# Teensy36_CAN_Bus.net
KiCad netlist of a schematic drawn in EAGLE
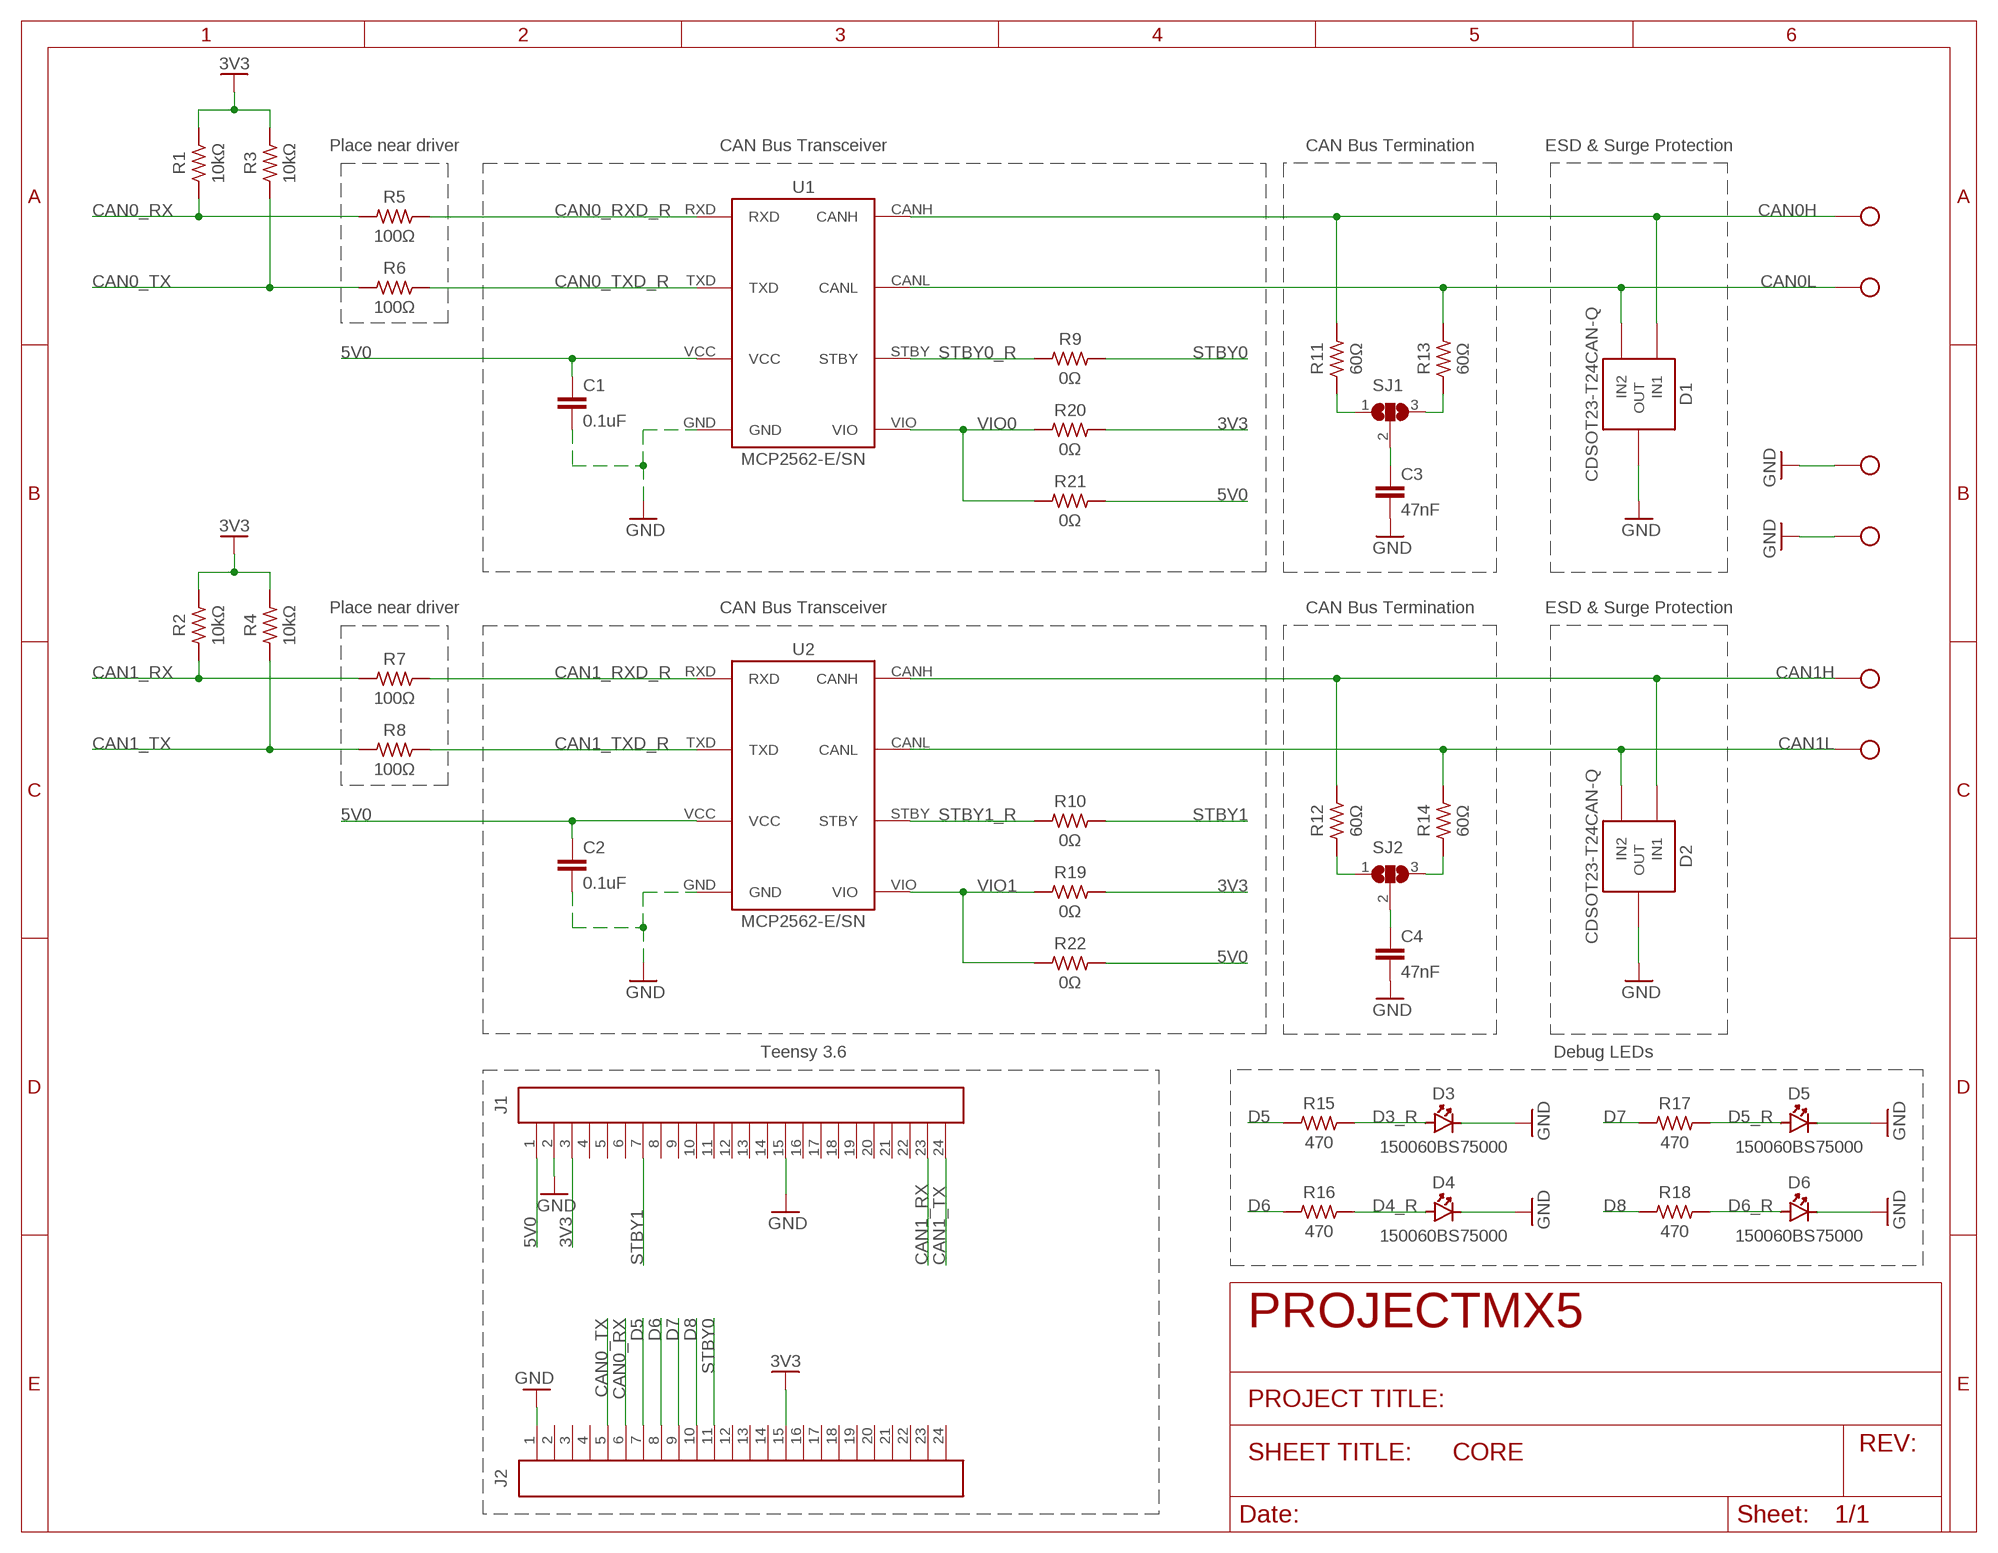
[diagram p0: schematic, sheet 1]

(export (version "E")
  (design (tool "Eeschema 10.0.6"))
  (components
    (comp (ref "C1")
      (value "0.1uF")
      (footprint "eagle-import:CAP-0603")
      (libsource (lib "eagle-import") (part "CAPACITOR0603"))
    )
    (comp (ref "C2")
      (value "0.1uF")
      (footprint "eagle-import:CAP-0603")
      (libsource (lib "eagle-import") (part "CAPACITOR0603"))
    )
    (comp (ref "C3")
      (value "47nF")
      (footprint "eagle-import:CAP-0603")
      (libsource (lib "eagle-import") (part "CAPACITOR0603"))
    )
    (comp (ref "C4")
      (value "47nF")
      (footprint "eagle-import:CAP-0603")
      (libsource (lib "eagle-import") (part "CAPACITOR0603"))
    )
    (comp (ref "D1")
      (value "CDSOT23-T24CAN-Q")
      (footprint "eagle-import:BOURNS_CDSOT23-T24CAN-Q")
      (libsource (lib "eagle-import") (part "BOURNS_CDSOT23-T24CAN-Q"))
    )
    (comp (ref "D2")
      (value "CDSOT23-T24CAN-Q")
      (footprint "eagle-import:BOURNS_CDSOT23-T24CAN-Q")
      (libsource (lib "eagle-import") (part "BOURNS_CDSOT23-T24CAN-Q"))
    )
    (comp (ref "D3")
      (value "LED_BLUE_0603_WURTH")
      (footprint "eagle-import:WURTH_0603_LED")
      (fields (field (name "PN") "150060BS75000") (field (name "MFG") "WURTH ELEKTRONIK"))
      (libsource (lib "eagle-import") (part "LED_BLUE_0603_WURTH"))
    )
    (comp (ref "D4")
      (value "LED_BLUE_0603_WURTH")
      (footprint "eagle-import:WURTH_0603_LED")
      (fields (field (name "PN") "150060BS75000") (field (name "MFG") "WURTH ELEKTRONIK"))
      (libsource (lib "eagle-import") (part "LED_BLUE_0603_WURTH"))
    )
    (comp (ref "D5")
      (value "LED_BLUE_0603_WURTH")
      (footprint "eagle-import:WURTH_0603_LED")
      (fields (field (name "PN") "150060BS75000") (field (name "MFG") "WURTH ELEKTRONIK"))
      (libsource (lib "eagle-import") (part "LED_BLUE_0603_WURTH"))
    )
    (comp (ref "D6")
      (value "LED_BLUE_0603_WURTH")
      (footprint "eagle-import:WURTH_0603_LED")
      (fields (field (name "PN") "150060BS75000") (field (name "MFG") "WURTH ELEKTRONIK"))
      (libsource (lib "eagle-import") (part "LED_BLUE_0603_WURTH"))
    )
    (comp (ref "J1")
      (value "CONN_24PIN_VERT")
      (footprint "eagle-import:CONN_100MIL_24_PIN")
      (libsource (lib "eagle-import") (part "CONN_24PIN_VERT"))
    )
    (comp (ref "J2")
      (value "CONN_24PIN_VERT")
      (footprint "eagle-import:CONN_100MIL_24_PIN")
      (libsource (lib "eagle-import") (part "CONN_24PIN_VERT"))
    )
    (comp (ref "J3")
      (value "SOLDER_POINT")
      (footprint "eagle-import:SMD_PAD_100X200")
      (libsource (lib "eagle-import") (part "SOLDER_POINT"))
    )
    (comp (ref "J4")
      (value "SOLDER_POINT")
      (footprint "eagle-import:SMD_PAD_100X200")
      (libsource (lib "eagle-import") (part "SOLDER_POINT"))
    )
    (comp (ref "J5")
      (value "SOLDER_POINT")
      (footprint "eagle-import:SMD_PAD_100X200")
      (libsource (lib "eagle-import") (part "SOLDER_POINT"))
    )
    (comp (ref "J6")
      (value "SOLDER_POINT")
      (footprint "eagle-import:SMD_PAD_100X200")
      (libsource (lib "eagle-import") (part "SOLDER_POINT"))
    )
    (comp (ref "J7")
      (value "SOLDER_POINT")
      (footprint "eagle-import:SMD_PAD_100X200")
      (libsource (lib "eagle-import") (part "SOLDER_POINT"))
    )
    (comp (ref "J8")
      (value "SOLDER_POINT")
      (footprint "eagle-import:SMD_PAD_100X200")
      (libsource (lib "eagle-import") (part "SOLDER_POINT"))
    )
    (comp (ref "R1")
      (value "10kΩ")
      (footprint "eagle-import:REST-0603")
      (libsource (lib "eagle-import") (part "RESISTOR"))
    )
    (comp (ref "R2")
      (value "10kΩ")
      (footprint "eagle-import:REST-0603")
      (libsource (lib "eagle-import") (part "RESISTOR"))
    )
    (comp (ref "R3")
      (value "10kΩ")
      (footprint "eagle-import:REST-0603")
      (libsource (lib "eagle-import") (part "RESISTOR"))
    )
    (comp (ref "R4")
      (value "10kΩ")
      (footprint "eagle-import:REST-0603")
      (libsource (lib "eagle-import") (part "RESISTOR"))
    )
    (comp (ref "R5")
      (value "100Ω")
      (footprint "eagle-import:REST-0603")
      (libsource (lib "eagle-import") (part "RESISTOR"))
    )
    (comp (ref "R6")
      (value "100Ω")
      (footprint "eagle-import:REST-0603")
      (libsource (lib "eagle-import") (part "RESISTOR"))
    )
    (comp (ref "R7")
      (value "100Ω")
      (footprint "eagle-import:REST-0603")
      (libsource (lib "eagle-import") (part "RESISTOR"))
    )
    (comp (ref "R8")
      (value "100Ω")
      (footprint "eagle-import:REST-0603")
      (libsource (lib "eagle-import") (part "RESISTOR"))
    )
    (comp (ref "R9")
      (value "0Ω")
      (footprint "eagle-import:REST-0603")
      (libsource (lib "eagle-import") (part "RESISTOR"))
    )
    (comp (ref "R10")
      (value "0Ω")
      (footprint "eagle-import:REST-0603")
      (libsource (lib "eagle-import") (part "RESISTOR"))
    )
    (comp (ref "R11")
      (value "60Ω")
      (footprint "eagle-import:REST-0603")
      (libsource (lib "eagle-import") (part "RESISTOR"))
    )
    (comp (ref "R12")
      (value "60Ω")
      (footprint "eagle-import:REST-0603")
      (libsource (lib "eagle-import") (part "RESISTOR"))
    )
    (comp (ref "R13")
      (value "60Ω")
      (footprint "eagle-import:REST-0603")
      (libsource (lib "eagle-import") (part "RESISTOR"))
    )
    (comp (ref "R14")
      (value "60Ω")
      (footprint "eagle-import:REST-0603")
      (libsource (lib "eagle-import") (part "RESISTOR"))
    )
    (comp (ref "R15")
      (value "470")
      (footprint "eagle-import:REST-0603")
      (fields (field (name "MFG") "PANASONIC"))
      (libsource (lib "eagle-import") (part "470OHM-0603-1%-1/10W"))
    )
    (comp (ref "R16")
      (value "470")
      (footprint "eagle-import:REST-0603")
      (fields (field (name "MFG") "PANASONIC"))
      (libsource (lib "eagle-import") (part "470OHM-0603-1%-1/10W"))
    )
    (comp (ref "R17")
      (value "470")
      (footprint "eagle-import:REST-0603")
      (fields (field (name "MFG") "PANASONIC"))
      (libsource (lib "eagle-import") (part "470OHM-0603-1%-1/10W"))
    )
    (comp (ref "R18")
      (value "470")
      (footprint "eagle-import:REST-0603")
      (fields (field (name "MFG") "PANASONIC"))
      (libsource (lib "eagle-import") (part "470OHM-0603-1%-1/10W"))
    )
    (comp (ref "R19")
      (value "0Ω")
      (footprint "eagle-import:REST-0603")
      (libsource (lib "eagle-import") (part "RESISTOR"))
    )
    (comp (ref "R20")
      (value "0Ω")
      (footprint "eagle-import:REST-0603")
      (libsource (lib "eagle-import") (part "RESISTOR"))
    )
    (comp (ref "R21")
      (value "0Ω")
      (footprint "eagle-import:REST-0603")
      (libsource (lib "eagle-import") (part "RESISTOR"))
    )
    (comp (ref "R22")
      (value "0Ω")
      (footprint "eagle-import:REST-0603")
      (libsource (lib "eagle-import") (part "RESISTOR"))
    )
    (comp (ref "SJ1")
      (value "SJ2W")
      (footprint "eagle-import:SJ_2")
      (libsource (lib "eagle-import") (part "SJ2W"))
    )
    (comp (ref "SJ2")
      (value "SJ2W")
      (footprint "eagle-import:SJ_2")
      (libsource (lib "eagle-import") (part "SJ2W"))
    )
    (comp (ref "U1")
      (value "SN65HVD230DR")
      (footprint "eagle-import:MICROCHIP_MCP2562")
      (fields (field (name "PN") "MCP2562-E/SN") (field (name "MFG") "MICROCHIP"))
      (libsource (lib "eagle-import") (part "MICROCHIP_MCP2562-E/SN"))
    )
    (comp (ref "U2")
      (value "SN65HVD230DR")
      (footprint "eagle-import:MICROCHIP_MCP2562")
      (fields (field (name "PN") "MCP2562-E/SN") (field (name "MFG") "MICROCHIP"))
      (libsource (lib "eagle-import") (part "MICROCHIP_MCP2562-E/SN"))
    )
  )
  (nets
    (net (code "1") (name "/5V0") (class "Default")
      (node (ref "C1") (pin "1") (pinfunction "1_1") (pintype "passive"))
      (node (ref "C2") (pin "1") (pinfunction "1_1") (pintype "passive"))
      (node (ref "J1") (pin "1") (pinfunction "1_1") (pintype "bidirectional"))
      (node (ref "R21") (pin "2") (pinfunction "2_2") (pintype "bidirectional"))
      (node (ref "R22") (pin "2") (pinfunction "2_2") (pintype "bidirectional"))
      (node (ref "U1") (pin "VCC") (pinfunction "VCC_VCC") (pintype "bidirectional"))
      (node (ref "U2") (pin "VCC") (pinfunction "VCC_VCC") (pintype "bidirectional"))
    )
    (net (code "2") (name "/CAN0H") (class "Default")
      (node (ref "D1") (pin "IN2") (pinfunction "IN1_IN2") (pintype "bidirectional"))
      (node (ref "J5") (pin "P$1") (pinfunction "IN_P$1") (pintype "bidirectional"))
      (node (ref "R11") (pin "2") (pinfunction "2_2") (pintype "bidirectional"))
      (node (ref "U1") (pin "CANH") (pinfunction "CANH_CANH") (pintype "bidirectional"))
    )
    (net (code "3") (name "/CAN0L") (class "Default")
      (node (ref "D1") (pin "IN1") (pinfunction "IN2_IN1") (pintype "bidirectional"))
      (node (ref "J6") (pin "P$1") (pinfunction "IN_P$1") (pintype "bidirectional"))
      (node (ref "R13") (pin "2") (pinfunction "2_2") (pintype "bidirectional"))
      (node (ref "U1") (pin "CANL") (pinfunction "CANL_CANL") (pintype "bidirectional"))
    )
    (net (code "4") (name "/CAN0_RX") (class "Default")
      (node (ref "J2") (pin "6") (pinfunction "6_6") (pintype "bidirectional"))
      (node (ref "R1") (pin "1") (pinfunction "1_1") (pintype "bidirectional"))
      (node (ref "R5") (pin "1") (pinfunction "1_1") (pintype "bidirectional"))
    )
    (net (code "5") (name "/CAN0_RXD_R") (class "Default")
      (node (ref "R5") (pin "2") (pinfunction "2_2") (pintype "bidirectional"))
      (node (ref "U1") (pin "RXD") (pinfunction "RXD_RXD") (pintype "output"))
    )
    (net (code "6") (name "/CAN0_TX") (class "Default")
      (node (ref "J2") (pin "5") (pinfunction "5_5") (pintype "bidirectional"))
      (node (ref "R3") (pin "1") (pinfunction "1_1") (pintype "bidirectional"))
      (node (ref "R6") (pin "1") (pinfunction "1_1") (pintype "bidirectional"))
    )
    (net (code "7") (name "/CAN0_TXD_R") (class "Default")
      (node (ref "R6") (pin "2") (pinfunction "2_2") (pintype "bidirectional"))
      (node (ref "U1") (pin "TXD") (pinfunction "TXD_TXD") (pintype "input"))
    )
    (net (code "8") (name "/CAN1H") (class "Default")
      (node (ref "D2") (pin "IN2") (pinfunction "IN1_IN2") (pintype "bidirectional"))
      (node (ref "J3") (pin "P$1") (pinfunction "IN_P$1") (pintype "bidirectional"))
      (node (ref "R12") (pin "2") (pinfunction "2_2") (pintype "bidirectional"))
      (node (ref "U2") (pin "CANH") (pinfunction "CANH_CANH") (pintype "bidirectional"))
    )
    (net (code "9") (name "/CAN1L") (class "Default")
      (node (ref "D2") (pin "IN1") (pinfunction "IN2_IN1") (pintype "bidirectional"))
      (node (ref "J4") (pin "P$1") (pinfunction "IN_P$1") (pintype "bidirectional"))
      (node (ref "R14") (pin "2") (pinfunction "2_2") (pintype "bidirectional"))
      (node (ref "U2") (pin "CANL") (pinfunction "CANL_CANL") (pintype "bidirectional"))
    )
    (net (code "10") (name "/CAN1_RX") (class "Default")
      (node (ref "J1") (pin "23") (pinfunction "23_23") (pintype "bidirectional"))
      (node (ref "R2") (pin "1") (pinfunction "1_1") (pintype "bidirectional"))
      (node (ref "R7") (pin "1") (pinfunction "1_1") (pintype "bidirectional"))
    )
    (net (code "11") (name "/CAN1_RXD_R") (class "Default")
      (node (ref "R7") (pin "2") (pinfunction "2_2") (pintype "bidirectional"))
      (node (ref "U2") (pin "RXD") (pinfunction "RXD_RXD") (pintype "output"))
    )
    (net (code "12") (name "/CAN1_TX") (class "Default")
      (node (ref "J1") (pin "24") (pinfunction "24_24") (pintype "bidirectional"))
      (node (ref "R4") (pin "1") (pinfunction "1_1") (pintype "bidirectional"))
      (node (ref "R8") (pin "1") (pinfunction "1_1") (pintype "bidirectional"))
    )
    (net (code "13") (name "/CAN1_TXD_R") (class "Default")
      (node (ref "R8") (pin "2") (pinfunction "2_2") (pintype "bidirectional"))
      (node (ref "U2") (pin "TXD") (pinfunction "TXD_TXD") (pintype "input"))
    )
    (net (code "14") (name "/D3_R") (class "Default")
      (node (ref "D3") (pin "A") (pinfunction "A_A") (pintype "passive"))
      (node (ref "R15") (pin "2") (pinfunction "2_2") (pintype "bidirectional"))
    )
    (net (code "15") (name "/D4_R") (class "Default")
      (node (ref "D4") (pin "A") (pinfunction "A_A") (pintype "passive"))
      (node (ref "R16") (pin "2") (pinfunction "2_2") (pintype "bidirectional"))
    )
    (net (code "16") (name "/D5") (class "Default")
      (node (ref "J2") (pin "7") (pinfunction "7_7") (pintype "bidirectional"))
      (node (ref "R15") (pin "1") (pinfunction "1_1") (pintype "bidirectional"))
    )
    (net (code "17") (name "/D5_R") (class "Default")
      (node (ref "D5") (pin "A") (pinfunction "A_A") (pintype "passive"))
      (node (ref "R17") (pin "2") (pinfunction "2_2") (pintype "bidirectional"))
    )
    (net (code "18") (name "/D6") (class "Default")
      (node (ref "J2") (pin "8") (pinfunction "8_8") (pintype "bidirectional"))
      (node (ref "R16") (pin "1") (pinfunction "1_1") (pintype "bidirectional"))
    )
    (net (code "19") (name "/D6_R") (class "Default")
      (node (ref "D6") (pin "A") (pinfunction "A_A") (pintype "passive"))
      (node (ref "R18") (pin "2") (pinfunction "2_2") (pintype "bidirectional"))
    )
    (net (code "20") (name "/D7") (class "Default")
      (node (ref "J2") (pin "9") (pinfunction "9_9") (pintype "bidirectional"))
      (node (ref "R17") (pin "1") (pinfunction "1_1") (pintype "bidirectional"))
    )
    (net (code "21") (name "/D8") (class "Default")
      (node (ref "J2") (pin "10") (pinfunction "10_10") (pintype "bidirectional"))
      (node (ref "R18") (pin "1") (pinfunction "1_1") (pintype "bidirectional"))
    )
    (net (code "22") (name "/STBY0") (class "Default")
      (node (ref "J2") (pin "11") (pinfunction "11_11") (pintype "bidirectional"))
      (node (ref "R9") (pin "2") (pinfunction "2_2") (pintype "bidirectional"))
    )
    (net (code "23") (name "/STBY0_R") (class "Default")
      (node (ref "R9") (pin "1") (pinfunction "1_1") (pintype "bidirectional"))
      (node (ref "U1") (pin "STBY") (pinfunction "STBY_STBY") (pintype "input"))
    )
    (net (code "24") (name "/STBY1") (class "Default")
      (node (ref "J1") (pin "7") (pinfunction "7_7") (pintype "bidirectional"))
      (node (ref "R10") (pin "2") (pinfunction "2_2") (pintype "bidirectional"))
    )
    (net (code "25") (name "/STBY1_R") (class "Default")
      (node (ref "R10") (pin "1") (pinfunction "1_1") (pintype "bidirectional"))
      (node (ref "U2") (pin "STBY") (pinfunction "STBY_STBY") (pintype "input"))
    )
    (net (code "26") (name "/VIO0") (class "Default")
      (node (ref "R20") (pin "1") (pinfunction "1_1") (pintype "bidirectional"))
      (node (ref "R21") (pin "1") (pinfunction "1_1") (pintype "bidirectional"))
      (node (ref "U1") (pin "VIO") (pinfunction "VIO_VIO") (pintype "output"))
    )
    (net (code "27") (name "/VIO1") (class "Default")
      (node (ref "R19") (pin "1") (pinfunction "1_1") (pintype "bidirectional"))
      (node (ref "R22") (pin "1") (pinfunction "1_1") (pintype "bidirectional"))
      (node (ref "U2") (pin "VIO") (pinfunction "VIO_VIO") (pintype "output"))
    )
    (net (code "28") (name "GND") (class "Default")
      (node (ref "C1") (pin "2") (pinfunction "2_2") (pintype "passive"))
      (node (ref "C2") (pin "2") (pinfunction "2_2") (pintype "passive"))
      (node (ref "C3") (pin "2") (pinfunction "2_2") (pintype "passive"))
      (node (ref "C4") (pin "2") (pinfunction "2_2") (pintype "passive"))
      (node (ref "D1") (pin "COMMON") (pinfunction "OUT_COMMON") (pintype "bidirectional"))
      (node (ref "D2") (pin "COMMON") (pinfunction "OUT_COMMON") (pintype "bidirectional"))
      (node (ref "D3") (pin "C") (pinfunction "C_C") (pintype "passive"))
      (node (ref "D4") (pin "C") (pinfunction "C_C") (pintype "passive"))
      (node (ref "D5") (pin "C") (pinfunction "C_C") (pintype "passive"))
      (node (ref "D6") (pin "C") (pinfunction "C_C") (pintype "passive"))
      (node (ref "J1") (pin "15") (pinfunction "15_15") (pintype "bidirectional"))
      (node (ref "J1") (pin "2") (pinfunction "2_2") (pintype "bidirectional"))
      (node (ref "J2") (pin "1") (pinfunction "1_1") (pintype "bidirectional"))
      (node (ref "J7") (pin "P$1") (pinfunction "IN_P$1") (pintype "bidirectional"))
      (node (ref "J8") (pin "P$1") (pinfunction "IN_P$1") (pintype "bidirectional"))
      (node (ref "U1") (pin "GND") (pinfunction "GND_GND") (pintype "bidirectional"))
      (node (ref "U2") (pin "GND") (pinfunction "GND_GND") (pintype "bidirectional"))
    )
    (net (code "29") (name "Net-(C3-Pad1)") (class "Default")
      (node (ref "C3") (pin "1") (pinfunction "1_1") (pintype "passive"))
      (node (ref "SJ1") (pin "2") (pinfunction "2_2") (pintype "passive"))
    )
    (net (code "30") (name "Net-(C4-Pad1)") (class "Default")
      (node (ref "C4") (pin "1") (pinfunction "1_1") (pintype "passive"))
      (node (ref "SJ2") (pin "2") (pinfunction "2_2") (pintype "passive"))
    )
    (net (code "31") (name "Net-(R11-Pad1)") (class "Default")
      (node (ref "R11") (pin "1") (pinfunction "1_1") (pintype "bidirectional"))
      (node (ref "SJ1") (pin "1") (pinfunction "1_1") (pintype "passive"))
    )
    (net (code "32") (name "Net-(R12-Pad1)") (class "Default")
      (node (ref "R12") (pin "1") (pinfunction "1_1") (pintype "bidirectional"))
      (node (ref "SJ2") (pin "1") (pinfunction "1_1") (pintype "passive"))
    )
    (net (code "33") (name "Net-(R13-Pad1)") (class "Default")
      (node (ref "R13") (pin "1") (pinfunction "1_1") (pintype "bidirectional"))
      (node (ref "SJ1") (pin "3") (pinfunction "3_3") (pintype "passive"))
    )
    (net (code "34") (name "Net-(R14-Pad1)") (class "Default")
      (node (ref "R14") (pin "1") (pinfunction "1_1") (pintype "bidirectional"))
      (node (ref "SJ2") (pin "3") (pinfunction "3_3") (pintype "passive"))
    )
    (net (code "35") (name "POWER_PORT") (class "Default")
      (node (ref "J1") (pin "3") (pinfunction "3_3") (pintype "bidirectional"))
      (node (ref "J2") (pin "15") (pinfunction "15_15") (pintype "bidirectional"))
      (node (ref "R1") (pin "2") (pinfunction "2_2") (pintype "bidirectional"))
      (node (ref "R19") (pin "2") (pinfunction "2_2") (pintype "bidirectional"))
      (node (ref "R2") (pin "2") (pinfunction "2_2") (pintype "bidirectional"))
      (node (ref "R20") (pin "2") (pinfunction "2_2") (pintype "bidirectional"))
      (node (ref "R3") (pin "2") (pinfunction "2_2") (pintype "bidirectional"))
      (node (ref "R4") (pin "2") (pinfunction "2_2") (pintype "bidirectional"))
    )
    (net (code "36") (name "unconnected-(J1-Pad4)") (class "Default")
      (node (ref "J1") (pin "4") (pinfunction "4_4") (pintype "bidirectional"))
    )
    (net (code "37") (name "unconnected-(J1-Pad5)") (class "Default")
      (node (ref "J1") (pin "5") (pinfunction "5_5") (pintype "bidirectional"))
    )
    (net (code "38") (name "unconnected-(J1-Pad6)") (class "Default")
      (node (ref "J1") (pin "6") (pinfunction "6_6") (pintype "bidirectional"))
    )
    (net (code "39") (name "unconnected-(J1-Pad8)") (class "Default")
      (node (ref "J1") (pin "8") (pinfunction "8_8") (pintype "bidirectional"))
    )
    (net (code "40") (name "unconnected-(J1-Pad9)") (class "Default")
      (node (ref "J1") (pin "9") (pinfunction "9_9") (pintype "bidirectional"))
    )
    (net (code "41") (name "unconnected-(J1-Pad10)") (class "Default")
      (node (ref "J1") (pin "10") (pinfunction "10_10") (pintype "bidirectional"))
    )
    (net (code "42") (name "unconnected-(J1-Pad11)") (class "Default")
      (node (ref "J1") (pin "11") (pinfunction "11_11") (pintype "bidirectional"))
    )
    (net (code "43") (name "unconnected-(J1-Pad12)") (class "Default")
      (node (ref "J1") (pin "12") (pinfunction "12_12") (pintype "bidirectional"))
    )
    (net (code "44") (name "unconnected-(J1-Pad13)") (class "Default")
      (node (ref "J1") (pin "13") (pinfunction "13_13") (pintype "bidirectional"))
    )
    (net (code "45") (name "unconnected-(J1-Pad14)") (class "Default")
      (node (ref "J1") (pin "14") (pinfunction "14_14") (pintype "bidirectional"))
    )
    (net (code "46") (name "unconnected-(J1-Pad16)") (class "Default")
      (node (ref "J1") (pin "16") (pinfunction "16_16") (pintype "bidirectional"))
    )
    (net (code "47") (name "unconnected-(J1-Pad17)") (class "Default")
      (node (ref "J1") (pin "17") (pinfunction "17_17") (pintype "bidirectional"))
    )
    (net (code "48") (name "unconnected-(J1-Pad18)") (class "Default")
      (node (ref "J1") (pin "18") (pinfunction "18_18") (pintype "bidirectional"))
    )
    (net (code "49") (name "unconnected-(J1-Pad19)") (class "Default")
      (node (ref "J1") (pin "19") (pinfunction "19_19") (pintype "bidirectional"))
    )
    (net (code "50") (name "unconnected-(J1-Pad20)") (class "Default")
      (node (ref "J1") (pin "20") (pinfunction "20_20") (pintype "bidirectional"))
    )
    (net (code "51") (name "unconnected-(J1-Pad21)") (class "Default")
      (node (ref "J1") (pin "21") (pinfunction "21_21") (pintype "bidirectional"))
    )
    (net (code "52") (name "unconnected-(J1-Pad22)") (class "Default")
      (node (ref "J1") (pin "22") (pinfunction "22_22") (pintype "bidirectional"))
    )
    (net (code "53") (name "unconnected-(J2-Pad2)") (class "Default")
      (node (ref "J2") (pin "2") (pinfunction "2_2") (pintype "bidirectional"))
    )
    (net (code "54") (name "unconnected-(J2-Pad3)") (class "Default")
      (node (ref "J2") (pin "3") (pinfunction "3_3") (pintype "bidirectional"))
    )
    (net (code "55") (name "unconnected-(J2-Pad4)") (class "Default")
      (node (ref "J2") (pin "4") (pinfunction "4_4") (pintype "bidirectional"))
    )
    (net (code "56") (name "unconnected-(J2-Pad12)") (class "Default")
      (node (ref "J2") (pin "12") (pinfunction "12_12") (pintype "bidirectional"))
    )
    (net (code "57") (name "unconnected-(J2-Pad13)") (class "Default")
      (node (ref "J2") (pin "13") (pinfunction "13_13") (pintype "bidirectional"))
    )
    (net (code "58") (name "unconnected-(J2-Pad14)") (class "Default")
      (node (ref "J2") (pin "14") (pinfunction "14_14") (pintype "bidirectional"))
    )
    (net (code "59") (name "unconnected-(J2-Pad16)") (class "Default")
      (node (ref "J2") (pin "16") (pinfunction "16_16") (pintype "bidirectional"))
    )
    (net (code "60") (name "unconnected-(J2-Pad17)") (class "Default")
      (node (ref "J2") (pin "17") (pinfunction "17_17") (pintype "bidirectional"))
    )
    (net (code "61") (name "unconnected-(J2-Pad18)") (class "Default")
      (node (ref "J2") (pin "18") (pinfunction "18_18") (pintype "bidirectional"))
    )
    (net (code "62") (name "unconnected-(J2-Pad19)") (class "Default")
      (node (ref "J2") (pin "19") (pinfunction "19_19") (pintype "bidirectional"))
    )
    (net (code "63") (name "unconnected-(J2-Pad20)") (class "Default")
      (node (ref "J2") (pin "20") (pinfunction "20_20") (pintype "bidirectional"))
    )
    (net (code "64") (name "unconnected-(J2-Pad21)") (class "Default")
      (node (ref "J2") (pin "21") (pinfunction "21_21") (pintype "bidirectional"))
    )
    (net (code "65") (name "unconnected-(J2-Pad22)") (class "Default")
      (node (ref "J2") (pin "22") (pinfunction "22_22") (pintype "bidirectional"))
    )
    (net (code "66") (name "unconnected-(J2-Pad23)") (class "Default")
      (node (ref "J2") (pin "23") (pinfunction "23_23") (pintype "bidirectional"))
    )
    (net (code "67") (name "unconnected-(J2-Pad24)") (class "Default")
      (node (ref "J2") (pin "24") (pinfunction "24_24") (pintype "bidirectional"))
    )
  )
)
